# v4_6.net
KiCad netlist of a schematic drawn in EAGLE
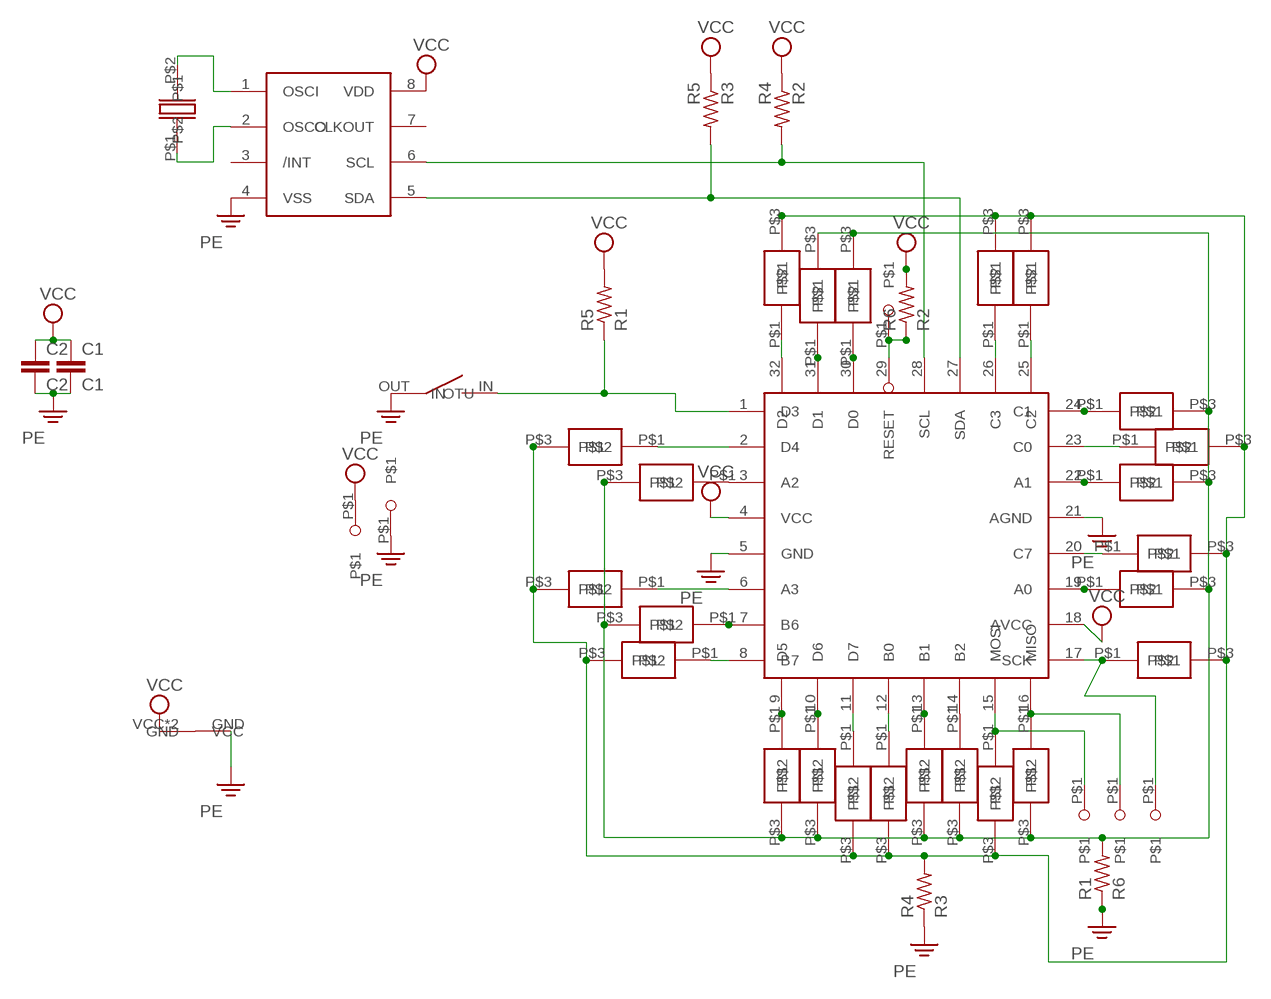
[diagram p0: schematic, sheet 1]

(export (version "E")
  (design (tool "Eeschema 10.0.6"))
  (components
    (comp (ref "C1")
      (value "C1")
      (footprint "eagle-import:C0805K")
      (libsource (lib "eagle-import") (part "C-EUC0805K"))
    )
    (comp (ref "C2")
      (value "C2")
      (footprint "eagle-import:C0805K")
      (libsource (lib "eagle-import") (part "C-EUC0805K"))
    )
    (comp (ref "R1")
      (value "R6")
      (footprint "eagle-import:R0805")
      (libsource (lib "eagle-import") (part "R-US_R0805"))
    )
    (comp (ref "R2")
      (value "R4")
      (footprint "eagle-import:R0805")
      (libsource (lib "eagle-import") (part "R-US_R0805"))
    )
    (comp (ref "R3")
      (value "R5")
      (footprint "eagle-import:R0805")
      (libsource (lib "eagle-import") (part "R-US_R0805"))
    )
    (comp (ref "R4")
      (value "R3")
      (footprint "eagle-import:R0805")
      (libsource (lib "eagle-import") (part "R-US_R0805"))
    )
    (comp (ref "R5")
      (value "R1")
      (footprint "eagle-import:R0805")
      (libsource (lib "eagle-import") (part "R-US_R0805"))
    )
    (comp (ref "R6")
      (value "R2")
      (footprint "eagle-import:R0805")
      (libsource (lib "eagle-import") (part "R-US_R0805"))
    )
    (comp (ref "U$1")
      (value "SMDLED")
      (footprint "eagle-import:SMDLED")
      (libsource (lib "eagle-import") (part "SMDLED"))
    )
    (comp (ref "U$2")
      (value "SMDLED")
      (footprint "eagle-import:SMDLED")
      (libsource (lib "eagle-import") (part "SMDLED"))
    )
    (comp (ref "U$3")
      (value "SMDLED")
      (footprint "eagle-import:SMDLED")
      (libsource (lib "eagle-import") (part "SMDLED"))
    )
    (comp (ref "U$4")
      (value "SMDLED")
      (footprint "eagle-import:SMDLED")
      (libsource (lib "eagle-import") (part "SMDLED"))
    )
    (comp (ref "U$5")
      (value "SMDLED")
      (footprint "eagle-import:SMDLED")
      (libsource (lib "eagle-import") (part "SMDLED"))
    )
    (comp (ref "U$6")
      (value "SMDLED")
      (footprint "eagle-import:SMDLED")
      (libsource (lib "eagle-import") (part "SMDLED"))
    )
    (comp (ref "U$7")
      (value "SMDLED")
      (footprint "eagle-import:SMDLED")
      (libsource (lib "eagle-import") (part "SMDLED"))
    )
    (comp (ref "U$8")
      (value "SMDLED")
      (footprint "eagle-import:SMDLED")
      (libsource (lib "eagle-import") (part "SMDLED"))
    )
    (comp (ref "U$9")
      (value "SMDLED")
      (footprint "eagle-import:SMDLED")
      (libsource (lib "eagle-import") (part "SMDLED"))
    )
    (comp (ref "U$10")
      (value "SMDLED")
      (footprint "eagle-import:SMDLED")
      (libsource (lib "eagle-import") (part "SMDLED"))
    )
    (comp (ref "U$11")
      (value "SMDLED")
      (footprint "eagle-import:SMDLED")
      (libsource (lib "eagle-import") (part "SMDLED"))
    )
    (comp (ref "U$12")
      (value "SMDLED")
      (footprint "eagle-import:SMDLED")
      (libsource (lib "eagle-import") (part "SMDLED"))
    )
    (comp (ref "U$13")
      (value "SMDLED")
      (footprint "eagle-import:SMDLED")
      (libsource (lib "eagle-import") (part "SMDLED"))
    )
    (comp (ref "U$14")
      (value "SMDLED")
      (footprint "eagle-import:SMDLED")
      (libsource (lib "eagle-import") (part "SMDLED"))
    )
    (comp (ref "U$15")
      (value "SMDLED")
      (footprint "eagle-import:SMDLED")
      (libsource (lib "eagle-import") (part "SMDLED"))
    )
    (comp (ref "U$16")
      (value "SMDLED")
      (footprint "eagle-import:SMDLED")
      (libsource (lib "eagle-import") (part "SMDLED"))
    )
    (comp (ref "U$17")
      (value "SMDLED")
      (footprint "eagle-import:SMDLED")
      (libsource (lib "eagle-import") (part "SMDLED"))
    )
    (comp (ref "U$18")
      (value "SMDLED")
      (footprint "eagle-import:SMDLED")
      (libsource (lib "eagle-import") (part "SMDLED"))
    )
    (comp (ref "U$19")
      (value "SMDLED")
      (footprint "eagle-import:SMDLED")
      (libsource (lib "eagle-import") (part "SMDLED"))
    )
    (comp (ref "U$20")
      (value "SMDLED")
      (footprint "eagle-import:SMDLED")
      (libsource (lib "eagle-import") (part "SMDLED"))
    )
    (comp (ref "U$21")
      (value "SMDLED")
      (footprint "eagle-import:SMDLED")
      (libsource (lib "eagle-import") (part "SMDLED"))
    )
    (comp (ref "U$22")
      (value "SMDLED")
      (footprint "eagle-import:SMDLED")
      (libsource (lib "eagle-import") (part "SMDLED"))
    )
    (comp (ref "U$23")
      (value "SMDLED")
      (footprint "eagle-import:SMDLED")
      (libsource (lib "eagle-import") (part "SMDLED"))
    )
    (comp (ref "U$24")
      (value "SMDLED")
      (footprint "eagle-import:SMDLED")
      (libsource (lib "eagle-import") (part "SMDLED"))
    )
    (comp (ref "U$25")
      (value "ATTINY88")
      (footprint "eagle-import:32-TQFT")
      (libsource (lib "eagle-import") (part "ATTINY88"))
    )
    (comp (ref "U$26")
      (value "PAD50")
      (footprint "eagle-import:PAD50")
      (libsource (lib "eagle-import") (part "PAD50"))
    )
    (comp (ref "U$27")
      (value "BAT2009")
      (footprint "eagle-import:BAT2009")
      (libsource (lib "eagle-import") (part "BAT2009"))
    )
    (comp (ref "U$28")
      (value "INT2")
      (footprint "eagle-import:INT2")
      (libsource (lib "eagle-import") (part "INT2"))
    )
    (comp (ref "U$29")
      (value "SMDCRYSTAL")
      (footprint "eagle-import:SMDCRYSTAL")
      (libsource (lib "eagle-import") (part "SMDCRYSTAL"))
    )
    (comp (ref "U$30")
      (value "RTC-SOIC")
      (footprint "eagle-import:8-SOIC")
      (libsource (lib "eagle-import") (part "RTC-SOIC"))
    )
    (comp (ref "U$31")
      (value "PAD50")
      (footprint "eagle-import:PAD50")
      (libsource (lib "eagle-import") (part "PAD50"))
    )
    (comp (ref "U$32")
      (value "PAD50")
      (footprint "eagle-import:PAD50")
      (libsource (lib "eagle-import") (part "PAD50"))
    )
    (comp (ref "U$33")
      (value "PAD50")
      (footprint "eagle-import:PAD50")
      (libsource (lib "eagle-import") (part "PAD50"))
    )
    (comp (ref "U$34")
      (value "PAD50")
      (footprint "eagle-import:PAD50")
      (libsource (lib "eagle-import") (part "PAD50"))
    )
    (comp (ref "U$35")
      (value "PAD50")
      (footprint "eagle-import:PAD50")
      (libsource (lib "eagle-import") (part "PAD50"))
    )
  )
  (nets
    (net (code "1") (name "Net-(U$1-P$2)") (class "Default")
      (node (ref "R4") (pin "2") (pinfunction "2_2") (pintype "passive"))
      (node (ref "U$1") (pin "P$3") (pinfunction "P$2_P$3") (pintype "bidirectional"))
      (node (ref "U$10") (pin "P$3") (pinfunction "P$2_P$3") (pintype "bidirectional"))
      (node (ref "U$11") (pin "P$3") (pinfunction "P$2_P$3") (pintype "bidirectional"))
      (node (ref "U$14") (pin "P$3") (pinfunction "P$2_P$3") (pintype "bidirectional"))
      (node (ref "U$15") (pin "P$3") (pinfunction "P$2_P$3") (pintype "bidirectional"))
      (node (ref "U$17") (pin "P$3") (pinfunction "P$2_P$3") (pintype "bidirectional"))
      (node (ref "U$20") (pin "P$3") (pinfunction "P$2_P$3") (pintype "bidirectional"))
      (node (ref "U$22") (pin "P$3") (pinfunction "P$2_P$3") (pintype "bidirectional"))
      (node (ref "U$24") (pin "P$3") (pinfunction "P$2_P$3") (pintype "bidirectional"))
      (node (ref "U$4") (pin "P$3") (pinfunction "P$2_P$3") (pintype "bidirectional"))
      (node (ref "U$8") (pin "P$3") (pinfunction "P$2_P$3") (pintype "bidirectional"))
      (node (ref "U$9") (pin "P$3") (pinfunction "P$2_P$3") (pintype "bidirectional"))
    )
    (net (code "2") (name "Net-(U$12-P$2)") (class "Default")
      (node (ref "R1") (pin "2") (pinfunction "2_2") (pintype "passive"))
      (node (ref "U$12") (pin "P$3") (pinfunction "P$2_P$3") (pintype "bidirectional"))
      (node (ref "U$13") (pin "P$3") (pinfunction "P$2_P$3") (pintype "bidirectional"))
      (node (ref "U$16") (pin "P$3") (pinfunction "P$2_P$3") (pintype "bidirectional"))
      (node (ref "U$18") (pin "P$3") (pinfunction "P$2_P$3") (pintype "bidirectional"))
      (node (ref "U$19") (pin "P$3") (pinfunction "P$2_P$3") (pintype "bidirectional"))
      (node (ref "U$2") (pin "P$3") (pinfunction "P$2_P$3") (pintype "bidirectional"))
      (node (ref "U$21") (pin "P$3") (pinfunction "P$2_P$3") (pintype "bidirectional"))
      (node (ref "U$23") (pin "P$3") (pinfunction "P$2_P$3") (pintype "bidirectional"))
      (node (ref "U$3") (pin "P$3") (pinfunction "P$2_P$3") (pintype "bidirectional"))
      (node (ref "U$5") (pin "P$3") (pinfunction "P$2_P$3") (pintype "bidirectional"))
      (node (ref "U$6") (pin "P$3") (pinfunction "P$2_P$3") (pintype "bidirectional"))
      (node (ref "U$7") (pin "P$3") (pinfunction "P$2_P$3") (pintype "bidirectional"))
    )
    (net (code "3") (name "Net-(U$25-A0)") (class "Default")
      (node (ref "U$12") (pin "P$1") (pinfunction "P$1_P$1") (pintype "bidirectional"))
      (node (ref "U$25") (pin "19") (pinfunction "A0_19") (pintype "bidirectional"))
    )
    (net (code "4") (name "Net-(U$25-A1)") (class "Default")
      (node (ref "U$21") (pin "P$1") (pinfunction "P$1_P$1") (pintype "bidirectional"))
      (node (ref "U$25") (pin "22") (pinfunction "A1_22") (pintype "bidirectional"))
    )
    (net (code "5") (name "Net-(U$25-A2)") (class "Default")
      (node (ref "U$16") (pin "P$1") (pinfunction "P$1_P$1") (pintype "bidirectional"))
      (node (ref "U$25") (pin "3") (pinfunction "A2_3") (pintype "bidirectional"))
    )
    (net (code "6") (name "Net-(U$25-A3)") (class "Default")
      (node (ref "U$17") (pin "P$1") (pinfunction "P$1_P$1") (pintype "bidirectional"))
      (node (ref "U$25") (pin "6") (pinfunction "A3_6") (pintype "bidirectional"))
    )
    (net (code "7") (name "Net-(U$25-B0)") (class "Default")
      (node (ref "U$1") (pin "P$1") (pinfunction "P$1_P$1") (pintype "bidirectional"))
      (node (ref "U$25") (pin "12") (pinfunction "B0_12") (pintype "bidirectional"))
    )
    (net (code "8") (name "Net-(U$25-B1)") (class "Default")
      (node (ref "U$2") (pin "P$1") (pinfunction "P$1_P$1") (pintype "bidirectional"))
      (node (ref "U$25") (pin "13") (pinfunction "B1_13") (pintype "bidirectional"))
    )
    (net (code "9") (name "Net-(U$25-B2)") (class "Default")
      (node (ref "U$25") (pin "14") (pinfunction "B2_14") (pintype "bidirectional"))
      (node (ref "U$3") (pin "P$1") (pinfunction "P$1_P$1") (pintype "bidirectional"))
    )
    (net (code "10") (name "Net-(U$25-B6)") (class "Default")
      (node (ref "U$25") (pin "7") (pinfunction "B6_7") (pintype "bidirectional"))
      (node (ref "U$7") (pin "P$1") (pinfunction "P$1_P$1") (pintype "bidirectional"))
    )
    (net (code "11") (name "Net-(U$25-B7)") (class "Default")
      (node (ref "U$25") (pin "8") (pinfunction "B7_8") (pintype "bidirectional"))
      (node (ref "U$8") (pin "P$1") (pinfunction "P$1_P$1") (pintype "bidirectional"))
    )
    (net (code "12") (name "Net-(U$25-C0)") (class "Default")
      (node (ref "U$22") (pin "P$1") (pinfunction "P$1_P$1") (pintype "bidirectional"))
      (node (ref "U$25") (pin "23") (pinfunction "C0_23") (pintype "bidirectional"))
    )
    (net (code "13") (name "Net-(U$25-C1)") (class "Default")
      (node (ref "U$25") (pin "24") (pinfunction "C1_24") (pintype "bidirectional"))
      (node (ref "U$6") (pin "P$1") (pinfunction "P$1_P$1") (pintype "bidirectional"))
    )
    (net (code "14") (name "Net-(U$25-C2)") (class "Default")
      (node (ref "U$25") (pin "25") (pinfunction "C2_25") (pintype "bidirectional"))
      (node (ref "U$9") (pin "P$1") (pinfunction "P$1_P$1") (pintype "bidirectional"))
    )
    (net (code "15") (name "Net-(U$25-C3)") (class "Default")
      (node (ref "U$24") (pin "P$1") (pinfunction "P$1_P$1") (pintype "bidirectional"))
      (node (ref "U$25") (pin "26") (pinfunction "C3_26") (pintype "bidirectional"))
    )
    (net (code "16") (name "Net-(U$25-C7)") (class "Default")
      (node (ref "U$10") (pin "P$1") (pinfunction "P$1_P$1") (pintype "bidirectional"))
      (node (ref "U$25") (pin "20") (pinfunction "C7_20") (pintype "bidirectional"))
    )
    (net (code "17") (name "Net-(U$25-D0)") (class "Default")
      (node (ref "U$23") (pin "P$1") (pinfunction "P$1_P$1") (pintype "bidirectional"))
      (node (ref "U$25") (pin "30") (pinfunction "D0_30") (pintype "bidirectional"))
    )
    (net (code "18") (name "Net-(U$25-D1)") (class "Default")
      (node (ref "U$13") (pin "P$1") (pinfunction "P$1_P$1") (pintype "bidirectional"))
      (node (ref "U$25") (pin "31") (pinfunction "D1_31") (pintype "bidirectional"))
    )
    (net (code "19") (name "Net-(U$25-D2)") (class "Default")
      (node (ref "U$14") (pin "P$1") (pinfunction "P$1_P$1") (pintype "bidirectional"))
      (node (ref "U$25") (pin "32") (pinfunction "D2_32") (pintype "bidirectional"))
    )
    (net (code "20") (name "Net-(U$25-D3)") (class "Default")
      (node (ref "R5") (pin "1") (pinfunction "1_1") (pintype "passive"))
      (node (ref "U$25") (pin "1") (pinfunction "D3_1") (pintype "bidirectional"))
      (node (ref "U$28") (pin "IN") (pinfunction "IN_IN") (pintype "bidirectional"))
    )
    (net (code "21") (name "Net-(U$25-D4)") (class "Default")
      (node (ref "U$15") (pin "P$1") (pinfunction "P$1_P$1") (pintype "bidirectional"))
      (node (ref "U$25") (pin "2") (pinfunction "D4_2") (pintype "bidirectional"))
    )
    (net (code "22") (name "Net-(U$25-D5)") (class "Default")
      (node (ref "U$18") (pin "P$1") (pinfunction "P$1_P$1") (pintype "bidirectional"))
      (node (ref "U$25") (pin "9") (pinfunction "D5_9") (pintype "bidirectional"))
    )
    (net (code "23") (name "Net-(U$25-D6)") (class "Default")
      (node (ref "U$19") (pin "P$1") (pinfunction "P$1_P$1") (pintype "bidirectional"))
      (node (ref "U$25") (pin "10") (pinfunction "D6_10") (pintype "bidirectional"))
    )
    (net (code "24") (name "Net-(U$25-D7)") (class "Default")
      (node (ref "U$20") (pin "P$1") (pinfunction "P$1_P$1") (pintype "bidirectional"))
      (node (ref "U$25") (pin "11") (pinfunction "D7_11") (pintype "bidirectional"))
    )
    (net (code "25") (name "Net-(U$25-MISO)") (class "Default")
      (node (ref "U$25") (pin "16") (pinfunction "MISO_16") (pintype "bidirectional"))
      (node (ref "U$31") (pin "P$1") (pinfunction "P$1_P$1") (pintype "bidirectional"))
      (node (ref "U$5") (pin "P$1") (pinfunction "P$1_P$1") (pintype "bidirectional"))
    )
    (net (code "26") (name "Net-(U$25-MOSI)") (class "Default")
      (node (ref "U$25") (pin "15") (pinfunction "MOSI_15") (pintype "bidirectional"))
      (node (ref "U$32") (pin "P$1") (pinfunction "P$1_P$1") (pintype "bidirectional"))
      (node (ref "U$4") (pin "P$1") (pinfunction "P$1_P$1") (pintype "bidirectional"))
    )
    (net (code "27") (name "Net-(U$25-RESET)") (class "Default")
      (node (ref "R6") (pin "1") (pinfunction "1_1") (pintype "passive"))
      (node (ref "U$25") (pin "29") (pinfunction "RESET_29") (pintype "input"))
      (node (ref "U$26") (pin "P$1") (pinfunction "P$1_P$1") (pintype "bidirectional"))
    )
    (net (code "28") (name "Net-(U$25-SCK)") (class "Default")
      (node (ref "U$11") (pin "P$1") (pinfunction "P$1_P$1") (pintype "bidirectional"))
      (node (ref "U$25") (pin "17") (pinfunction "SCK_17") (pintype "bidirectional"))
      (node (ref "U$33") (pin "P$1") (pinfunction "P$1_P$1") (pintype "bidirectional"))
    )
    (net (code "29") (name "Net-(U$25-SCL)") (class "Default")
      (node (ref "R2") (pin "2") (pinfunction "2_2") (pintype "passive"))
      (node (ref "U$25") (pin "28") (pinfunction "SCL_28") (pintype "bidirectional"))
      (node (ref "U$30") (pin "6") (pinfunction "SCL_6") (pintype "input"))
    )
    (net (code "30") (name "Net-(U$25-SDA)") (class "Default")
      (node (ref "R3") (pin "2") (pinfunction "2_2") (pintype "passive"))
      (node (ref "U$25") (pin "27") (pinfunction "SDA_27") (pintype "bidirectional"))
      (node (ref "U$30") (pin "5") (pinfunction "SDA_5") (pintype "bidirectional"))
    )
    (net (code "31") (name "Net-(U$30-OSCI)") (class "Default")
      (node (ref "U$29") (pin "P$2") (pinfunction "P$2_P$2") (pintype "bidirectional"))
      (node (ref "U$30") (pin "1") (pinfunction "OSCI_1") (pintype "input"))
    )
    (net (code "32") (name "Net-(U$30-OSCO)") (class "Default")
      (node (ref "U$29") (pin "P$1") (pinfunction "P$1_P$1") (pintype "bidirectional"))
      (node (ref "U$30") (pin "2") (pinfunction "OSCO_2") (pintype "output"))
    )
    (net (code "33") (name "PE") (class "Default")
      (node (ref "C1") (pin "2") (pinfunction "2_2") (pintype "passive"))
      (node (ref "C2") (pin "2") (pinfunction "2_2") (pintype "passive"))
      (node (ref "R1") (pin "1") (pinfunction "1_1") (pintype "passive"))
      (node (ref "R4") (pin "1") (pinfunction "1_1") (pintype "passive"))
      (node (ref "U$25") (pin "21") (pinfunction "AGND_21") (pintype "power_in"))
      (node (ref "U$25") (pin "5") (pinfunction "GND_5") (pintype "power_in"))
      (node (ref "U$27") (pin "GND") (pinfunction "GND_GND") (pintype "bidirectional"))
      (node (ref "U$28") (pin "OUT") (pinfunction "OTU_OUT") (pintype "bidirectional"))
      (node (ref "U$30") (pin "4") (pinfunction "VSS_4") (pintype "power_in"))
      (node (ref "U$34") (pin "P$1") (pinfunction "P$1_P$1") (pintype "bidirectional"))
    )
    (net (code "34") (name "VCC") (class "Default")
      (node (ref "C1") (pin "1") (pinfunction "1_1") (pintype "passive"))
      (node (ref "C2") (pin "1") (pinfunction "1_1") (pintype "passive"))
      (node (ref "R2") (pin "1") (pinfunction "1_1") (pintype "passive"))
      (node (ref "R3") (pin "1") (pinfunction "1_1") (pintype "passive"))
      (node (ref "R5") (pin "2") (pinfunction "2_2") (pintype "passive"))
      (node (ref "R6") (pin "2") (pinfunction "2_2") (pintype "passive"))
      (node (ref "U$25") (pin "18") (pinfunction "AVCC_18") (pintype "power_in"))
      (node (ref "U$25") (pin "4") (pinfunction "VCC_4") (pintype "power_in"))
      (node (ref "U$27") (pin "VCC") (pinfunction "VCC_VCC") (pintype "bidirectional"))
      (node (ref "U$27") (pin "VCC2") (pinfunction "VCC_VCC2") (pintype "bidirectional"))
      (node (ref "U$30") (pin "8") (pinfunction "VDD_8") (pintype "power_in"))
      (node (ref "U$35") (pin "P$1") (pinfunction "P$1_P$1") (pintype "bidirectional"))
    )
    (net (code "35") (name "unconnected-(U$30-CLKOUT-Pad7)") (class "Default")
      (node (ref "U$30") (pin "7") (pinfunction "CLKOUT_7") (pintype "output"))
    )
    (net (code "36") (name "unconnected-(U$30-{slash}INT-Pad3)") (class "Default")
      (node (ref "U$30") (pin "3") (pinfunction "/INT_3") (pintype "output"))
    )
  )
)
